# Audio.net
KiCad netlist of a schematic drawn in Altium Designer
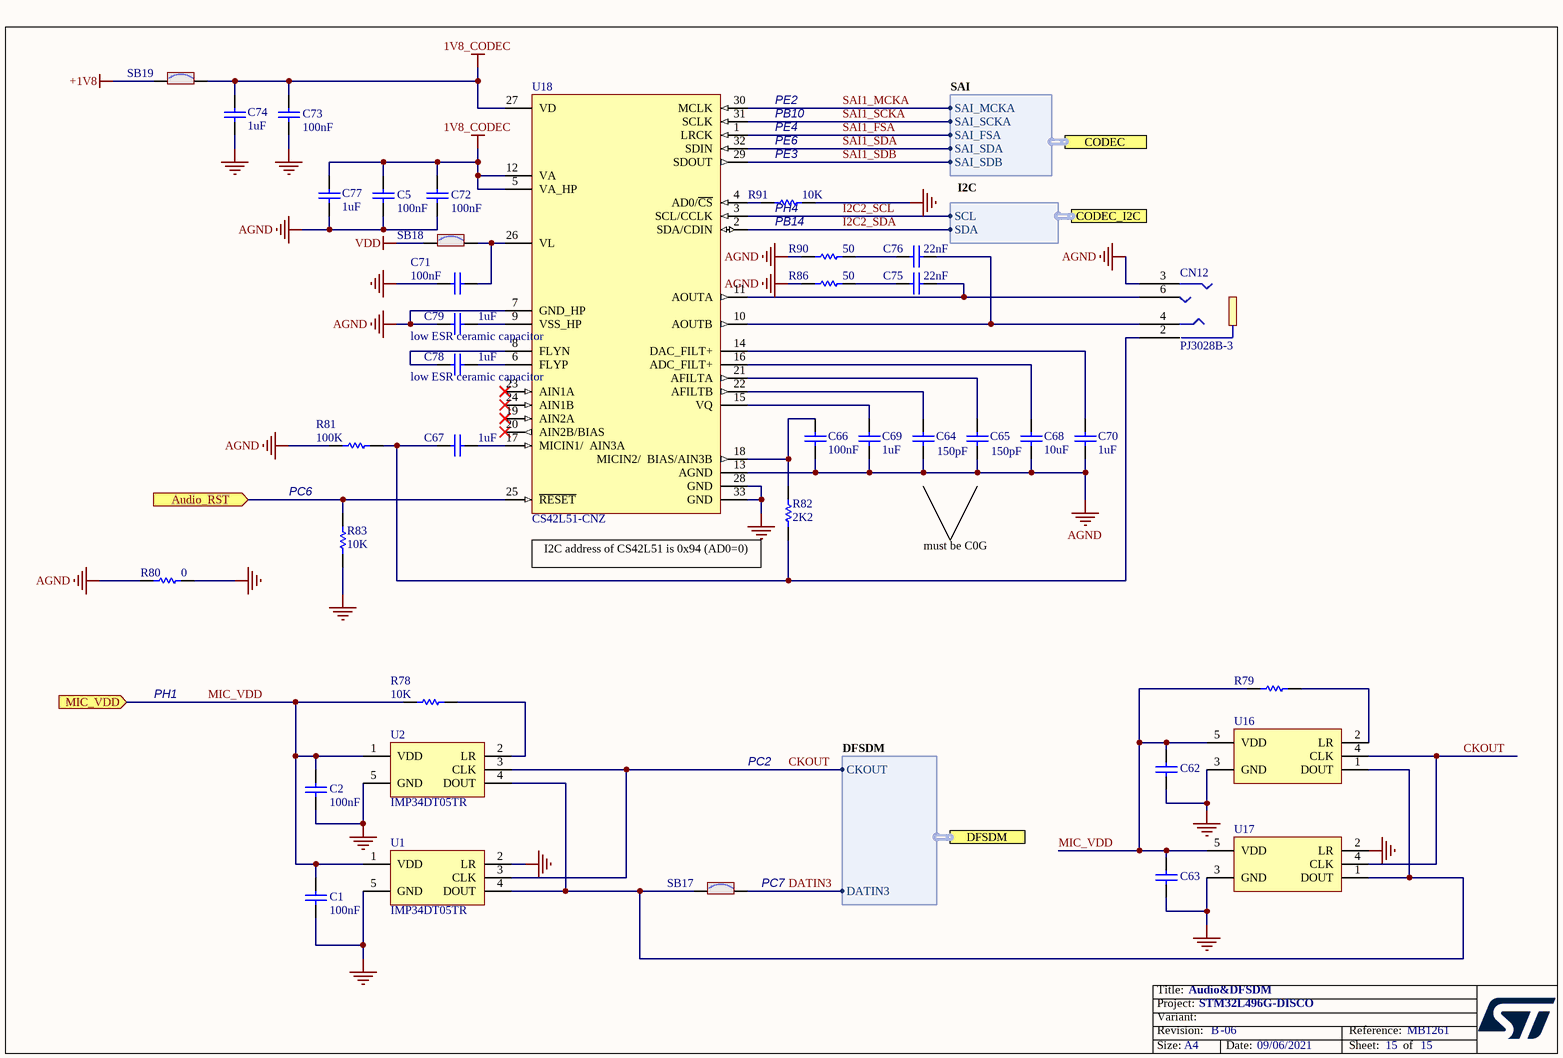
[diagram p0: Audio.SchDoc]

(export (version "E")
  (design (tool "Eeschema 10.0.6"))
  (components
    (comp (ref "C1")
      (value "100nF")
      (footprint "0603C")
      (description "Capacitor,100nF,10%,16V,X7R,0603,YAGEO")
      (fields (field (name "Comment") "CC0603KRX7R7BB104") (field (name "PUBLISHER") "Altium Limited"))
      (libsource (lib "Miscellaneous Devices") (part "Cap"))
    )
    (comp (ref "C2")
      (value "100nF")
      (footprint "0603C")
      (description "Capacitor,100nF,10%,16V,X7R,0603,YAGEO")
      (fields (field (name "Comment") "CC0603KRX7R7BB104") (field (name "PUBLISHER") "Altium Limited"))
      (libsource (lib "Miscellaneous Devices") (part "Cap"))
    )
    (comp (ref "C5")
      (value "100nF")
      (footprint "0603C")
      (description "Capacitor,100nF,10%,16V,X7R,0603,YAGEO")
      (fields (field (name "Comment") "CC0603KRX7R7BB104") (field (name "PUBLISHER") "Altium Limited"))
      (libsource (lib "Miscellaneous Devices") (part "Cap"))
    )
    (comp (ref "C62")
      (value "~")
      (footprint "0603C")
      (description "Capacitor,100nF,10%,16V,X7R,0603,YAGEO")
      (fields (field (name "PUBLISHER") "Altium Limited"))
      (libsource (lib "Miscellaneous Devices") (part "Cap"))
    )
    (comp (ref "C63")
      (value "~")
      (footprint "0603C")
      (description "Capacitor,100nF,10%,16V,X7R,0603,YAGEO")
      (fields (field (name "PUBLISHER") "Altium Limited"))
      (libsource (lib "Miscellaneous Devices") (part "Cap"))
    )
    (comp (ref "C64")
      (value "150pF")
      (footprint "0603C")
      (description "Capacitor,150pF,0603,50V,5%,NPO")
      (fields (field (name "Comment") "CC0603JRNPO9BN151") (field (name "PUBLISHER") "Altium Limited"))
      (libsource (lib "Miscellaneous Devices") (part "Cap"))
    )
    (comp (ref "C65")
      (value "150pF")
      (footprint "0603C")
      (description "Capacitor,150pF,0603,50V,5%,NPO")
      (fields (field (name "Comment") "CC0603JRNPO9BN151") (field (name "PUBLISHER") "Altium Limited"))
      (libsource (lib "Miscellaneous Devices") (part "Cap"))
    )
    (comp (ref "C66")
      (value "100nF")
      (footprint "0603C")
      (description "Capacitor,100nF,10%,16V,X7R,0603,YAGEO")
      (fields (field (name "Comment") "CC0603KRX7R7BB104") (field (name "PUBLISHER") "Altium Limited"))
      (libsource (lib "Miscellaneous Devices") (part "Cap"))
    )
    (comp (ref "C67")
      (value "1uF")
      (footprint "0603C")
      (description "Capacitor,1uF,0603,16V,10%,X5R,YAGEO")
      (fields (field (name "Comment") "CC0603KRX5R7BB105") (field (name "PUBLISHER") "Altium Limited"))
      (libsource (lib "Miscellaneous Devices") (part "Cap"))
    )
    (comp (ref "C68")
      (value "10uF")
      (footprint "0603C")
      (description "Capacitor,10uF,10%,10V,X5R,0603,C1608X5R1A106K080AC")
      (fields (field (name "Comment") "C1608X5R1A106K080AC") (field (name "PUBLISHER") "Altium Limited"))
      (libsource (lib "Miscellaneous Devices") (part "Cap"))
    )
    (comp (ref "C69")
      (value "1uF")
      (footprint "0603C")
      (description "Capacitor,1uF,0603,16V,10%,X5R,YAGEO")
      (fields (field (name "Comment") "CC0603KRX5R7BB105") (field (name "PUBLISHER") "Altium Limited"))
      (libsource (lib "Miscellaneous Devices") (part "Cap"))
    )
    (comp (ref "C70")
      (value "1uF")
      (footprint "0603C")
      (description "Capacitor,1uF,0603,16V,10%,X5R,YAGEO")
      (fields (field (name "Comment") "CC0603KRX5R7BB105") (field (name "PUBLISHER") "Altium Limited"))
      (libsource (lib "Miscellaneous Devices") (part "Cap"))
    )
    (comp (ref "C71")
      (value "100nF")
      (footprint "0603C")
      (description "Capacitor,100nF,10%,16V,X7R,0603,YAGEO")
      (fields (field (name "Comment") "CC0603KRX7R7BB104") (field (name "PUBLISHER") "Altium Limited"))
      (libsource (lib "Miscellaneous Devices") (part "Cap"))
    )
    (comp (ref "C72")
      (value "100nF")
      (footprint "0603C")
      (description "Capacitor,100nF,10%,16V,X7R,0603,YAGEO")
      (fields (field (name "Comment") "CC0603KRX7R7BB104") (field (name "PUBLISHER") "Altium Limited"))
      (libsource (lib "Miscellaneous Devices") (part "Cap"))
    )
    (comp (ref "C73")
      (value "100nF")
      (footprint "0603C")
      (description "Capacitor,100nF,10%,16V,X7R,0603,YAGEO")
      (fields (field (name "Comment") "CC0603KRX7R7BB104") (field (name "PUBLISHER") "Altium Limited"))
      (libsource (lib "Miscellaneous Devices") (part "Cap"))
    )
    (comp (ref "C74")
      (value "1uF")
      (footprint "0603C")
      (description "Capacitor,1uF,0603,16V,10%,X5R,YAGEO")
      (fields (field (name "Comment") "CC0603KRX5R7BB105") (field (name "PUBLISHER") "Altium Limited"))
      (libsource (lib "Miscellaneous Devices") (part "Cap"))
    )
    (comp (ref "C75")
      (value "22nF")
      (footprint "0603C")
      (description "Capacitor,22nF,10%,25V,X7R,0603")
      (fields (field (name "Comment") "CC0603KRX7R8BB223") (field (name "PUBLISHER") "Altium Limited"))
      (libsource (lib "Miscellaneous Devices") (part "Cap"))
    )
    (comp (ref "C76")
      (value "22nF")
      (footprint "0603C")
      (description "Capacitor,22nF,10%,25V,X7R,0603")
      (fields (field (name "Comment") "CC0603KRX7R8BB223") (field (name "PUBLISHER") "Altium Limited"))
      (libsource (lib "Miscellaneous Devices") (part "Cap"))
    )
    (comp (ref "C77")
      (value "1uF")
      (footprint "0603C")
      (description "Capacitor,1uF,0603,16V,10%,X5R,YAGEO")
      (fields (field (name "Comment") "CC0603KRX5R7BB105") (field (name "PUBLISHER") "Altium Limited"))
      (libsource (lib "Miscellaneous Devices") (part "Cap"))
    )
    (comp (ref "C78")
      (value "1uF")
      (footprint "0603C")
      (description "Capacitor,1uF,0603,16V,10%,X5R,YAGEO")
      (fields (field (name "Comment") "CC0603KRX5R7BB105") (field (name "PUBLISHER") "Altium Limited"))
      (libsource (lib "Miscellaneous Devices") (part "Cap"))
    )
    (comp (ref "C79")
      (value "1uF")
      (footprint "0603C")
      (description "Capacitor,1uF,0603,16V,10%,X5R,YAGEO")
      (fields (field (name "Comment") "CC0603KRX5R7BB105") (field (name "PUBLISHER") "Altium Limited"))
      (libsource (lib "Miscellaneous Devices") (part "Cap"))
    )
    (comp (ref "CN12") (value "PJ3028B-3") (footprint "PJ3028B") (libsource (lib "MB786") (part "PJ3028B-3")))
    (comp (ref "R78")
      (value "10K")
      (footprint "0603R")
      (description "Resistor,10K,0603,1%,YAGEO")
      (fields (field (name "Comment") "RC0603FR-0710KL") (field (name "PUBLISHER") "Altium Limited"))
      (libsource (lib "Miscellaneous Devices") (part "res1"))
    )
    (comp (ref "R79")
      (value "~")
      (footprint "0603R")
      (description "Resistor,10K,0603,1%,YAGEO")
      (fields (field (name "PUBLISHER") "Altium Limited"))
      (libsource (lib "Miscellaneous Devices") (part "res1"))
    )
    (comp (ref "R80")
      (value "0")
      (footprint "0603R")
      (description "Resistor, 0 ,0603,1%,YAGEO")
      (fields (field (name "Comment") "RC0603JR-070RL") (field (name "PUBLISHER") "Altium Limited"))
      (libsource (lib "Miscellaneous Devices") (part "res1"))
    )
    (comp (ref "R81")
      (value "100K")
      (footprint "0603R")
      (description "Resistor,100K,0603,1%,YAGEO")
      (fields (field (name "Comment") "RC0603FR-07100KL") (field (name "PUBLISHER") "Altium Limited"))
      (libsource (lib "Miscellaneous Devices") (part "res1"))
    )
    (comp (ref "R82")
      (value "2K2")
      (footprint "0603R")
      (description "Resistor,2.2K,0603,1%,YAGEO")
      (fields (field (name "Comment") "RC0603FR-072K2L") (field (name "PUBLISHER") "Altium Limited"))
      (libsource (lib "Miscellaneous Devices") (part "res1"))
    )
    (comp (ref "R83")
      (value "10K")
      (footprint "0603R")
      (description "Resistor,10K,0603,1%,YAGEO")
      (fields (field (name "Comment") "RC0603FR-0710KL") (field (name "PUBLISHER") "Altium Limited"))
      (libsource (lib "Miscellaneous Devices") (part "res1"))
    )
    (comp (ref "R86")
      (value "50")
      (footprint "0603R")
      (description "Resistor,50R,0603,1%,YAGEO")
      (fields (field (name "Comment") "RC0603FR-0750RL") (field (name "PUBLISHER") "Altium Limited"))
      (libsource (lib "Miscellaneous Devices") (part "res1"))
    )
    (comp (ref "R90")
      (value "50")
      (footprint "0603R")
      (description "Resistor,50R,0603,1%,YAGEO")
      (fields (field (name "Comment") "RC0603FR-0750RL") (field (name "PUBLISHER") "Altium Limited"))
      (libsource (lib "Miscellaneous Devices") (part "res1"))
    )
    (comp (ref "R91")
      (value "10K")
      (footprint "0603R")
      (description "Resistor,10K,0603,1%,YAGEO")
      (fields (field (name "Comment") "RC0603FR-0710KL") (field (name "PUBLISHER") "Altium Limited"))
      (libsource (lib "Miscellaneous Devices") (part "res1"))
    )
    (comp (ref "SB17")
      (value "Solder Bridge ON")
      (footprint "SB_0603")
      (libsource (lib "MCD_TOOLS") (part "SB_ON"))
    )
    (comp (ref "SB18")
      (value "Solder Bridge ON")
      (footprint "SB_0603")
      (libsource (lib "MCD_TOOLS") (part "SB_ON"))
    )
    (comp (ref "SB19")
      (value "Solder Bridge ON")
      (footprint "SB_0603")
      (libsource (lib "MCD_TOOLS") (part "SB_ON"))
    )
    (comp (ref "U1")
      (value "IMP34DT05TR")
      (footprint "MIC_HCLGA_3X4X1_4LD")
      (description "MEMS audio sensor omnidirectional digital microphone for industrial applications")
      (fields (field (name "INTERNAL_PART_NUMBER") "MCD-01715") (field (name "BMS_PART_NUMBER") "9177995"))
      (libsource (lib "MCD_PARTS_database") (part "IMP34DT05TR"))
    )
    (comp (ref "U2")
      (value "IMP34DT05TR")
      (footprint "MIC_HCLGA_3X4X1_4LD")
      (description "MEMS audio sensor omnidirectional digital microphone for industrial applications")
      (fields (field (name "INTERNAL_PART_NUMBER") "MCD-01715") (field (name "BMS_PART_NUMBER") "9177995"))
      (libsource (lib "MCD_PARTS_database") (part "IMP34DT05TR"))
    )
    (comp (ref "U16")
      (value "~")
      (footprint "RHLGA5LD")
      (description "MEMS micro")
      (fields (field (name "PUBLISHER") "STM"))
      (libsource (lib "Big Orga") (part "MP23DB01MM"))
    )
    (comp (ref "U17")
      (value "~")
      (footprint "RHLGA5LD")
      (description "MEMS micro")
      (fields (field (name "PUBLISHER") "STM"))
      (libsource (lib "Big Orga") (part "MP23DB01MM"))
    )
    (comp (ref "U18")
      (value "CS42L51-CNZ")
      (footprint "QFN32_0R5_5X5")
      (description "Low-Power, Stereo Codec with Headphone Amp")
      (libsource (lib "Big Orga") (part "CS42L51-CNZ"))
    )
  )
  (nets
    (net (code "4") (name "+1V8") (class "Default")
      (node (ref "SB19") (pin "1") (pinfunction "1_1") (pintype "passive"))
    )
    (net (code "5") (name "/Audio_RST") (class "Default")
      (node (ref "R83") (pin "2") (pinfunction "2_2") (pintype "passive"))
      (node (ref "U18") (pin "25") (pinfunction "~{RESET}_25") (pintype "input"))
    )
    (net (code "6") (name "/CKOUT") (class "Default")
      (node (ref "U1") (pin "3") (pinfunction "CLK_3") (pintype "passive"))
      (node (ref "U16") (pin "4") (pinfunction "CLK_4") (pintype "passive"))
      (node (ref "U17") (pin "4") (pinfunction "CLK_4") (pintype "passive"))
      (node (ref "U2") (pin "3") (pinfunction "CLK_3") (pintype "passive"))
    )
    (net (code "7") (name "/DATIN3") (class "Default")
      (node (ref "SB17") (pin "2") (pinfunction "2_2") (pintype "passive"))
    )
    (net (code "8") (name "/I2C2_SCL") (class "Default")
      (node (ref "U18") (pin "3") (pinfunction "SCL/CCLK_3") (pintype "input"))
    )
    (net (code "9") (name "/I2C2_SDA") (class "Default")
      (node (ref "U18") (pin "2") (pinfunction "SDA/CDIN_2") (pintype "bidirectional"))
    )
    (net (code "10") (name "/MIC_VDD") (class "Default")
      (node (ref "C1") (pin "1") (pinfunction "1_1") (pintype "passive"))
      (node (ref "C2") (pin "1") (pinfunction "1_1") (pintype "passive"))
      (node (ref "C62") (pin "1") (pinfunction "1_1") (pintype "passive"))
      (node (ref "C63") (pin "1") (pinfunction "1_1") (pintype "passive"))
      (node (ref "R78") (pin "2") (pinfunction "2_2") (pintype "passive"))
      (node (ref "R79") (pin "2") (pinfunction "2_2") (pintype "passive"))
      (node (ref "U1") (pin "1") (pinfunction "VDD_1") (pintype "passive"))
      (node (ref "U16") (pin "5") (pinfunction "VDD_5") (pintype "passive"))
      (node (ref "U17") (pin "5") (pinfunction "VDD_5") (pintype "passive"))
      (node (ref "U2") (pin "1") (pinfunction "VDD_1") (pintype "passive"))
    )
    (net (code "11") (name "/SAI1_FSA") (class "Default")
      (node (ref "U18") (pin "1") (pinfunction "LRCK_1") (pintype "input"))
    )
    (net (code "12") (name "/SAI1_MCKA") (class "Default")
      (node (ref "U18") (pin "30") (pinfunction "MCLK_30") (pintype "input"))
    )
    (net (code "13") (name "/SAI1_SCKA") (class "Default")
      (node (ref "U18") (pin "31") (pinfunction "SCLK_31") (pintype "input"))
    )
    (net (code "14") (name "/SAI1_SDA") (class "Default")
      (node (ref "U18") (pin "32") (pinfunction "SDIN_32") (pintype "input"))
    )
    (net (code "15") (name "/SAI1_SDB") (class "Default")
      (node (ref "U18") (pin "29") (pinfunction "SDOUT_29") (pintype "output"))
    )
    (net (code "19") (name "1V8_CODEC") (class "Default")
      (node (ref "C5") (pin "1") (pinfunction "1_1") (pintype "passive"))
      (node (ref "C72") (pin "1") (pinfunction "1_1") (pintype "passive"))
      (node (ref "C73") (pin "1") (pinfunction "1_1") (pintype "passive"))
      (node (ref "C74") (pin "1") (pinfunction "1_1") (pintype "passive"))
      (node (ref "C77") (pin "1") (pinfunction "1_1") (pintype "passive"))
      (node (ref "SB19") (pin "2") (pinfunction "2_2") (pintype "passive"))
      (node (ref "U18") (pin "12") (pinfunction "VA_12") (pintype "power_in"))
      (node (ref "U18") (pin "27") (pinfunction "VD_27") (pintype "power_in"))
      (node (ref "U18") (pin "5") (pinfunction "VA_HP_5") (pintype "power_in"))
    )
    (net (code "20") (name "AGND") (class "Default")
      (node (ref "C5") (pin "2") (pinfunction "2_2") (pintype "passive"))
      (node (ref "C64") (pin "2") (pinfunction "2_2") (pintype "passive"))
      (node (ref "C65") (pin "2") (pinfunction "2_2") (pintype "passive"))
      (node (ref "C66") (pin "1") (pinfunction "1_1") (pintype "passive"))
      (node (ref "C68") (pin "1") (pinfunction "1_1") (pintype "passive"))
      (node (ref "C69") (pin "1") (pinfunction "1_1") (pintype "passive"))
      (node (ref "C70") (pin "1") (pinfunction "1_1") (pintype "passive"))
      (node (ref "C72") (pin "2") (pinfunction "2_2") (pintype "passive"))
      (node (ref "C77") (pin "2") (pinfunction "2_2") (pintype "passive"))
      (node (ref "C79") (pin "1") (pinfunction "1_1") (pintype "passive"))
      (node (ref "CN12") (pin "3") (pintype "passive"))
      (node (ref "R80") (pin "2") (pinfunction "2_2") (pintype "passive"))
      (node (ref "R81") (pin "2") (pinfunction "2_2") (pintype "passive"))
      (node (ref "R86") (pin "2") (pinfunction "2_2") (pintype "passive"))
      (node (ref "R90") (pin "2") (pinfunction "2_2") (pintype "passive"))
      (node (ref "U18") (pin "13") (pinfunction "AGND_13") (pintype "power_in"))
      (node (ref "U18") (pin "7") (pinfunction "GND_HP_7") (pintype "power_in"))
    )
    (net (code "21") (name "GND") (class "Default")
      (node (ref "C1") (pin "2") (pinfunction "2_2") (pintype "passive"))
      (node (ref "C2") (pin "2") (pinfunction "2_2") (pintype "passive"))
      (node (ref "C62") (pin "2") (pinfunction "2_2") (pintype "passive"))
      (node (ref "C63") (pin "2") (pinfunction "2_2") (pintype "passive"))
      (node (ref "C71") (pin "1") (pinfunction "1_1") (pintype "passive"))
      (node (ref "C73") (pin "2") (pinfunction "2_2") (pintype "passive"))
      (node (ref "C74") (pin "2") (pinfunction "2_2") (pintype "passive"))
      (node (ref "R80") (pin "1") (pinfunction "1_1") (pintype "passive"))
      (node (ref "R83") (pin "1") (pinfunction "1_1") (pintype "passive"))
      (node (ref "R91") (pin "1") (pinfunction "1_1") (pintype "passive"))
      (node (ref "U1") (pin "2") (pinfunction "LR_2") (pintype "passive"))
      (node (ref "U1") (pin "5") (pinfunction "GND_5") (pintype "passive"))
      (node (ref "U16") (pin "3") (pinfunction "GND_3") (pintype "passive"))
      (node (ref "U17") (pin "2") (pinfunction "LR_2") (pintype "passive"))
      (node (ref "U17") (pin "3") (pinfunction "GND_3") (pintype "passive"))
      (node (ref "U18") (pin "28") (pinfunction "GND_28") (pintype "power_in"))
      (node (ref "U18") (pin "33") (pinfunction "GND_33") (pintype "power_in"))
      (node (ref "U2") (pin "5") (pinfunction "GND_5") (pintype "passive"))
    )
    (net (code "22") (name "Net-(C67-Pad1)") (class "Default")
      (node (ref "C67") (pin "1") (pinfunction "1_1") (pintype "passive"))
      (node (ref "CN12") (pin "2") (pintype "passive"))
      (node (ref "R81") (pin "1") (pinfunction "1_1") (pintype "passive"))
      (node (ref "R82") (pin "1") (pinfunction "1_1") (pintype "passive"))
    )
    (net (code "23") (name "Net-(C75-Pad2)") (class "Default")
      (node (ref "C75") (pin "2") (pinfunction "2_2") (pintype "passive"))
      (node (ref "R86") (pin "1") (pinfunction "1_1") (pintype "passive"))
    )
    (net (code "24") (name "Net-(C76-Pad2)") (class "Default")
      (node (ref "C76") (pin "2") (pinfunction "2_2") (pintype "passive"))
      (node (ref "R90") (pin "1") (pinfunction "1_1") (pintype "passive"))
    )
    (net (code "25") (name "Net-(U1-DOUT)") (class "Default")
      (node (ref "SB17") (pin "1") (pinfunction "1_1") (pintype "passive"))
      (node (ref "U1") (pin "4") (pinfunction "DOUT_4") (pintype "passive"))
      (node (ref "U16") (pin "1") (pinfunction "DOUT_1") (pintype "passive"))
      (node (ref "U17") (pin "1") (pinfunction "DOUT_1") (pintype "passive"))
      (node (ref "U2") (pin "4") (pinfunction "DOUT_4") (pintype "passive"))
    )
    (net (code "26") (name "Net-(U2-LR)") (class "Default")
      (node (ref "R78") (pin "1") (pinfunction "1_1") (pintype "passive"))
      (node (ref "U2") (pin "2") (pinfunction "LR_2") (pintype "passive"))
    )
    (net (code "27") (name "Net-(U16-LR)") (class "Default")
      (node (ref "R79") (pin "1") (pinfunction "1_1") (pintype "passive"))
      (node (ref "U16") (pin "2") (pinfunction "LR_2") (pintype "passive"))
    )
    (net (code "28") (name "Net-(U18-AD0{slash}~{CS})") (class "Default")
      (node (ref "R91") (pin "2") (pinfunction "2_2") (pintype "passive"))
      (node (ref "U18") (pin "4") (pinfunction "AD0/~{CS}_4") (pintype "input"))
    )
    (net (code "29") (name "Net-(U18-ADC_FILT+)") (class "Default")
      (node (ref "C68") (pin "2") (pinfunction "2_2") (pintype "passive"))
      (node (ref "U18") (pin "16") (pinfunction "ADC_FILT+_16") (pintype "power_in"))
    )
    (net (code "30") (name "Net-(U18-AFILTA)") (class "Default")
      (node (ref "C65") (pin "1") (pinfunction "1_1") (pintype "passive"))
      (node (ref "U18") (pin "21") (pinfunction "AFILTA_21") (pintype "output"))
    )
    (net (code "31") (name "Net-(U18-AFILTB)") (class "Default")
      (node (ref "C64") (pin "1") (pinfunction "1_1") (pintype "passive"))
      (node (ref "U18") (pin "22") (pinfunction "AFILTB_22") (pintype "output"))
    )
    (net (code "32") (name "Net-(U18-AOUTA)") (class "Default")
      (node (ref "C75") (pin "1") (pinfunction "1_1") (pintype "passive"))
      (node (ref "CN12") (pin "6") (pintype "passive"))
      (node (ref "U18") (pin "11") (pinfunction "AOUTA_11") (pintype "output"))
    )
    (net (code "33") (name "Net-(U18-AOUTB)") (class "Default")
      (node (ref "C76") (pin "1") (pinfunction "1_1") (pintype "passive"))
      (node (ref "CN12") (pin "4") (pintype "passive"))
      (node (ref "U18") (pin "10") (pinfunction "AOUTB_10") (pintype "output"))
    )
    (net (code "34") (name "Net-(U18-DAC_FILT+)") (class "Default")
      (node (ref "C70") (pin "2") (pinfunction "2_2") (pintype "passive"))
      (node (ref "U18") (pin "14") (pinfunction "DAC_FILT+_14") (pintype "power_in"))
    )
    (net (code "35") (name "Net-(U18-FLYN)") (class "Default")
      (node (ref "C78") (pin "1") (pinfunction "1_1") (pintype "passive"))
      (node (ref "U18") (pin "8") (pinfunction "FLYN_8") (pintype "passive"))
    )
    (net (code "36") (name "Net-(U18-FLYP)") (class "Default")
      (node (ref "C78") (pin "2") (pinfunction "2_2") (pintype "passive"))
      (node (ref "U18") (pin "6") (pinfunction "FLYP_6") (pintype "passive"))
    )
    (net (code "37") (name "Net-(U18-MICIN1{slash}__AIN3A)") (class "Default")
      (node (ref "C67") (pin "2") (pinfunction "2_2") (pintype "passive"))
      (node (ref "U18") (pin "17") (pinfunction "MICIN1/__AIN3A_17") (pintype "input"))
    )
    (net (code "38") (name "Net-(U18-MICIN2{slash}__BIAS{slash}AIN3B)") (class "Default")
      (node (ref "C66") (pin "2") (pinfunction "2_2") (pintype "passive"))
      (node (ref "R82") (pin "2") (pinfunction "2_2") (pintype "passive"))
      (node (ref "U18") (pin "18") (pinfunction "MICIN2/__BIAS/AIN3B_18") (pintype "output"))
    )
    (net (code "39") (name "Net-(U18-VL)") (class "Default")
      (node (ref "C71") (pin "2") (pinfunction "2_2") (pintype "passive"))
      (node (ref "SB18") (pin "2") (pinfunction "2_2") (pintype "passive"))
      (node (ref "U18") (pin "26") (pinfunction "VL_26") (pintype "power_in"))
    )
    (net (code "40") (name "Net-(U18-VQ)") (class "Default")
      (node (ref "C69") (pin "2") (pinfunction "2_2") (pintype "passive"))
      (node (ref "U18") (pin "15") (pinfunction "VQ_15") (pintype "power_in"))
    )
    (net (code "41") (name "Net-(U18-VSS_HP)") (class "Default")
      (node (ref "C79") (pin "2") (pinfunction "2_2") (pintype "passive"))
      (node (ref "U18") (pin "9") (pinfunction "VSS_HP_9") (pintype "power_in"))
    )
    (net (code "42") (name "VDD") (class "Default")
      (node (ref "SB18") (pin "1") (pinfunction "1_1") (pintype "passive"))
    )
    (net (code "43") (name "unconnected-(U18-AIN1A-Pad23)") (class "Default")
      (node (ref "U18") (pin "23") (pinfunction "AIN1A_23") (pintype "input+no_connect"))
    )
    (net (code "44") (name "unconnected-(U18-AIN1B-Pad24)") (class "Default")
      (node (ref "U18") (pin "24") (pinfunction "AIN1B_24") (pintype "input+no_connect"))
    )
    (net (code "45") (name "unconnected-(U18-AIN2A-Pad19)") (class "Default")
      (node (ref "U18") (pin "19") (pinfunction "AIN2A_19") (pintype "input+no_connect"))
    )
    (net (code "46") (name "unconnected-(U18-AIN2B{slash}BIAS-Pad20)") (class "Default")
      (node (ref "U18") (pin "20") (pinfunction "AIN2B/BIAS_20") (pintype "output+no_connect"))
    )
  )
)
